# FE2_1.net
KiCad netlist of a schematic drawn in Altium Designer
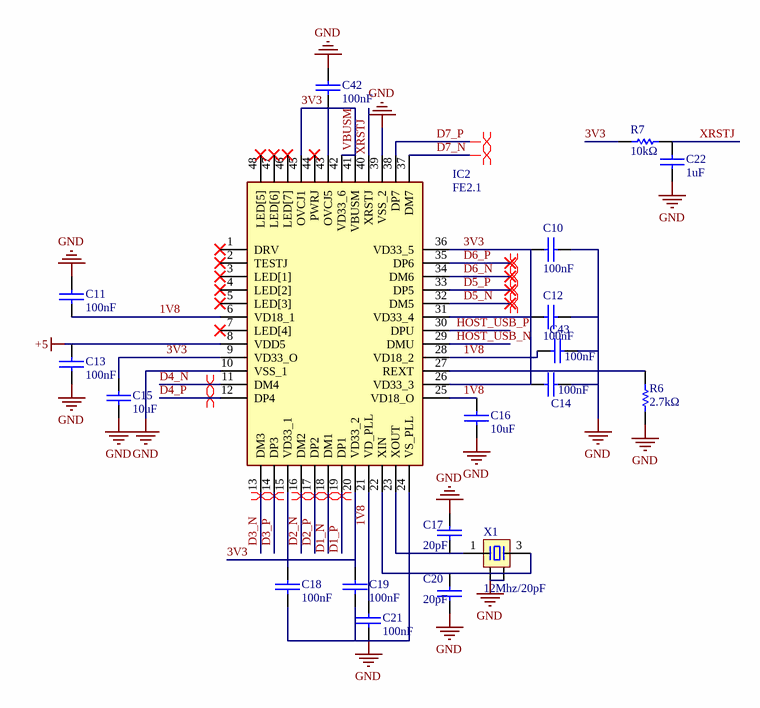
[diagram p0: FE2.1.SchDoc]

(export (version "E")
  (design (tool "Eeschema 10.0.6"))
  (components
    (comp (ref "C10")
      (value "100nF")
      (footprint "C_0402")
      (description "贴片电容")
      (libsource (lib "IntLib-Passive") (part "Cap_Chip"))
    )
    (comp (ref "C11")
      (value "100nF")
      (footprint "C_0402")
      (description "贴片电容")
      (libsource (lib "IntLib-Passive") (part "Cap_Chip"))
    )
    (comp (ref "C12")
      (value "100nF")
      (footprint "C_0402")
      (description "贴片电容")
      (libsource (lib "IntLib-Passive") (part "Cap_Chip"))
    )
    (comp (ref "C13")
      (value "100nF")
      (footprint "C_0402")
      (description "贴片电容")
      (libsource (lib "IntLib-Passive") (part "Cap_Chip"))
    )
    (comp (ref "C14")
      (value "100nF")
      (footprint "C_0402")
      (description "贴片电容")
      (libsource (lib "IntLib-Passive") (part "Cap_Chip"))
    )
    (comp (ref "C15")
      (value "10uF")
      (footprint "C_0603")
      (description "贴片电容")
      (libsource (lib "IntLib-Passive") (part "Cap_Chip"))
    )
    (comp (ref "C16")
      (value "10uF")
      (footprint "C_0603")
      (description "贴片电容")
      (libsource (lib "IntLib-Passive") (part "Cap_Chip"))
    )
    (comp (ref "C17")
      (value "20pF")
      (footprint "C_0402")
      (description "贴片电容")
      (libsource (lib "IntLib-Passive") (part "Cap_Chip"))
    )
    (comp (ref "C18")
      (value "100nF")
      (footprint "C_0402")
      (description "贴片电容")
      (libsource (lib "IntLib-Passive") (part "Cap_Chip"))
    )
    (comp (ref "C19")
      (value "100nF")
      (footprint "C_0402")
      (description "贴片电容")
      (libsource (lib "IntLib-Passive") (part "Cap_Chip"))
    )
    (comp (ref "C20")
      (value "20pF")
      (footprint "C_0402")
      (description "贴片电容")
      (libsource (lib "IntLib-Passive") (part "Cap_Chip"))
    )
    (comp (ref "C21")
      (value "100nF")
      (footprint "C_0402")
      (description "贴片电容")
      (libsource (lib "IntLib-Passive") (part "Cap_Chip"))
    )
    (comp (ref "C22")
      (value "1uF")
      (footprint "C_0402")
      (description "贴片电容")
      (libsource (lib "IntLib-Passive") (part "Cap_Chip"))
    )
    (comp (ref "C42")
      (value "100nF")
      (footprint "C_0402")
      (description "贴片电容")
      (libsource (lib "IntLib-Passive") (part "Cap_Chip"))
    )
    (comp (ref "C43")
      (value "100nF")
      (footprint "C_0402")
      (description "贴片电容")
      (libsource (lib "IntLib-Passive") (part "Cap_Chip"))
    )
    (comp (ref "IC2")
      (value "FE2.1")
      (footprint "IntLib-IC:LQFP48-48_7x7")
      (description "USB2.0 Hub 芯片")
      (fields (field (name "MANUFACTURER_PART_NUMBER") "FE2.1_QFP"))
      (libsource (lib "IntLib-IC") (part "FE2.1_QFP"))
    )
    (comp (ref "R6")
      (value "2.7kΩ")
      (footprint "R_0402")
      (description "贴片电阻")
      (libsource (lib "IntLib-Passive") (part "Res_Chip"))
    )
    (comp (ref "R7")
      (value "10kΩ")
      (footprint "R_0402")
      (description "贴片电阻")
      (libsource (lib "IntLib-Passive") (part "Res_Chip"))
    )
    (comp (ref "X1")
      (value "12Mhz/20pF")
      (footprint "XTAL_3225-4P")
      (description "4脚无源晶振")
      (fields (field (name "MANUFACTURER_PART_NUMBER") "X322512MSB4SI"))
      (libsource (lib "Active-Crystal") (part "Crystal_4P"))
    )
  )
  (nets
    (net (code "1") (name "+5") (class "Default")
      (node (ref "C13") (pin "1") (pinfunction "1_1") (pintype "passive"))
      (node (ref "IC2") (pin "8") (pinfunction "VDD5_8") (pintype "passive"))
    )
    (net (code "2") (name "/1V8") (class "Default")
      (node (ref "C11") (pin "2") (pinfunction "2_2") (pintype "passive"))
      (node (ref "C16") (pin "1") (pinfunction "1_1") (pintype "passive"))
      (node (ref "C21") (pin "1") (pinfunction "1_1") (pintype "passive"))
      (node (ref "C43") (pin "2") (pinfunction "2_2") (pintype "passive"))
      (node (ref "IC2") (pin "21") (pinfunction "VD_PLL_21") (pintype "passive"))
      (node (ref "IC2") (pin "25") (pinfunction "VD18_O_25") (pintype "passive"))
      (node (ref "IC2") (pin "28") (pinfunction "VD18_2_28") (pintype "passive"))
      (node (ref "IC2") (pin "6") (pinfunction "VD18_1_6") (pintype "passive"))
    )
    (net (code "3") (name "/3V3") (class "Default")
      (node (ref "C10") (pin "1") (pinfunction "1_1") (pintype "passive"))
      (node (ref "C12") (pin "2") (pinfunction "2_2") (pintype "passive"))
      (node (ref "C14") (pin "2") (pinfunction "2_2") (pintype "passive"))
      (node (ref "C15") (pin "2") (pinfunction "2_2") (pintype "passive"))
      (node (ref "C18") (pin "1") (pinfunction "1_1") (pintype "passive"))
      (node (ref "C19") (pin "1") (pinfunction "1_1") (pintype "passive"))
      (node (ref "C42") (pin "1") (pinfunction "1_1") (pintype "passive"))
      (node (ref "IC2") (pin "15") (pinfunction "VD33_1_15") (pintype "passive"))
      (node (ref "IC2") (pin "20") (pinfunction "VD33_2_20") (pintype "passive"))
      (node (ref "IC2") (pin "26") (pinfunction "VD33_3_26") (pintype "passive"))
      (node (ref "IC2") (pin "31") (pinfunction "VD33_4_31") (pintype "passive"))
      (node (ref "IC2") (pin "36") (pinfunction "VD33_5_36") (pintype "passive"))
      (node (ref "IC2") (pin "41") (pinfunction "VBUSM_41") (pintype "passive"))
      (node (ref "IC2") (pin "42") (pinfunction "VD33_6_42") (pintype "passive"))
      (node (ref "IC2") (pin "43") (pinfunction "OVCJ5_43") (pintype "passive"))
      (node (ref "IC2") (pin "45") (pinfunction "OVCJ1_45") (pintype "passive"))
      (node (ref "IC2") (pin "9") (pinfunction "VD33_O_9") (pintype "passive"))
      (node (ref "R7") (pin "2") (pinfunction "2_2") (pintype "passive"))
    )
    (net (code "4") (name "/D1_N") (class "Default")
      (node (ref "IC2") (pin "18") (pinfunction "DM1_18") (pintype "passive"))
    )
    (net (code "5") (name "/D1_P") (class "Default")
      (node (ref "IC2") (pin "19") (pinfunction "DP1_19") (pintype "passive"))
    )
    (net (code "6") (name "/D2_N") (class "Default")
      (node (ref "IC2") (pin "16") (pinfunction "DM2_16") (pintype "passive"))
    )
    (net (code "7") (name "/D2_P") (class "Default")
      (node (ref "IC2") (pin "17") (pinfunction "DP2_17") (pintype "passive"))
    )
    (net (code "8") (name "/D3_N") (class "Default")
      (node (ref "IC2") (pin "13") (pinfunction "DM3_13") (pintype "passive"))
    )
    (net (code "9") (name "/D3_P") (class "Default")
      (node (ref "IC2") (pin "14") (pinfunction "DP3_14") (pintype "passive"))
    )
    (net (code "10") (name "/D4_N") (class "Default")
      (node (ref "IC2") (pin "11") (pinfunction "DM4_11") (pintype "passive"))
    )
    (net (code "11") (name "/D4_P") (class "Default")
      (node (ref "IC2") (pin "12") (pinfunction "DP4_12") (pintype "passive"))
    )
    (net (code "12") (name "/D5_N") (class "Default")
      (node (ref "IC2") (pin "32") (pinfunction "DM5_32") (pintype "passive+no_connect"))
    )
    (net (code "13") (name "/D5_P") (class "Default")
      (node (ref "IC2") (pin "33") (pinfunction "DP5_33") (pintype "passive+no_connect"))
    )
    (net (code "14") (name "/D6_N") (class "Default")
      (node (ref "IC2") (pin "34") (pinfunction "DM6_34") (pintype "passive+no_connect"))
    )
    (net (code "15") (name "/D6_P") (class "Default")
      (node (ref "IC2") (pin "35") (pinfunction "DP6_35") (pintype "passive+no_connect"))
    )
    (net (code "16") (name "/D7_N") (class "Default")
      (node (ref "IC2") (pin "37") (pinfunction "DM7_37") (pintype "passive"))
    )
    (net (code "17") (name "/D7_P") (class "Default")
      (node (ref "IC2") (pin "38") (pinfunction "DP7_38") (pintype "passive"))
    )
    (net (code "18") (name "/HOST_USB_N") (class "Default")
      (node (ref "IC2") (pin "29") (pinfunction "DMU_29") (pintype "passive"))
    )
    (net (code "19") (name "/HOST_USB_P") (class "Default")
      (node (ref "IC2") (pin "30") (pinfunction "DPU_30") (pintype "passive"))
    )
    (net (code "20") (name "/XRSTJ") (class "Default")
      (node (ref "C22") (pin "2") (pinfunction "2_2") (pintype "passive"))
      (node (ref "IC2") (pin "40") (pinfunction "XRSTJ_40") (pintype "passive"))
      (node (ref "R7") (pin "1") (pinfunction "1_1") (pintype "passive"))
    )
    (net (code "21") (name "GND") (class "Default")
      (node (ref "C10") (pin "2") (pinfunction "2_2") (pintype "passive"))
      (node (ref "C11") (pin "1") (pinfunction "1_1") (pintype "passive"))
      (node (ref "C12") (pin "1") (pinfunction "1_1") (pintype "passive"))
      (node (ref "C13") (pin "2") (pinfunction "2_2") (pintype "passive"))
      (node (ref "C14") (pin "1") (pinfunction "1_1") (pintype "passive"))
      (node (ref "C15") (pin "1") (pinfunction "1_1") (pintype "passive"))
      (node (ref "C16") (pin "2") (pinfunction "2_2") (pintype "passive"))
      (node (ref "C17") (pin "2") (pinfunction "2_2") (pintype "passive"))
      (node (ref "C18") (pin "2") (pinfunction "2_2") (pintype "passive"))
      (node (ref "C19") (pin "2") (pinfunction "2_2") (pintype "passive"))
      (node (ref "C20") (pin "1") (pinfunction "1_1") (pintype "passive"))
      (node (ref "C21") (pin "2") (pinfunction "2_2") (pintype "passive"))
      (node (ref "C22") (pin "1") (pinfunction "1_1") (pintype "passive"))
      (node (ref "C42") (pin "2") (pinfunction "2_2") (pintype "passive"))
      (node (ref "C43") (pin "1") (pinfunction "1_1") (pintype "passive"))
      (node (ref "IC2") (pin "10") (pinfunction "VSS_1_10") (pintype "passive"))
      (node (ref "IC2") (pin "24") (pinfunction "VS_PLL_24") (pintype "passive"))
      (node (ref "IC2") (pin "39") (pinfunction "VSS_2_39") (pintype "passive"))
      (node (ref "R6") (pin "1") (pinfunction "1_1") (pintype "passive"))
      (node (ref "X1") (pin "2") (pinfunction "2_2") (pintype "passive"))
      (node (ref "X1") (pin "4") (pinfunction "4_4") (pintype "passive"))
    )
    (net (code "22") (name "Net-(IC2-REXT)") (class "Default")
      (node (ref "IC2") (pin "27") (pinfunction "REXT_27") (pintype "passive"))
      (node (ref "R6") (pin "2") (pinfunction "2_2") (pintype "passive"))
    )
    (net (code "23") (name "Net-(IC2-XIN)") (class "Default")
      (node (ref "C20") (pin "2") (pinfunction "2_2") (pintype "passive"))
      (node (ref "IC2") (pin "22") (pinfunction "XIN_22") (pintype "passive"))
      (node (ref "X1") (pin "3") (pinfunction "3_3") (pintype "passive"))
    )
    (net (code "24") (name "Net-(IC2-XOUT)") (class "Default")
      (node (ref "C17") (pin "1") (pinfunction "1_1") (pintype "passive"))
      (node (ref "IC2") (pin "23") (pinfunction "XOUT_23") (pintype "passive"))
      (node (ref "X1") (pin "1") (pinfunction "1_1") (pintype "passive"))
    )
    (net (code "25") (name "unconnected-(IC2-DRV-Pad1)") (class "Default")
      (node (ref "IC2") (pin "1") (pinfunction "DRV_1") (pintype "passive+no_connect"))
    )
    (net (code "26") (name "unconnected-(IC2-LED[1]-Pad3)") (class "Default")
      (node (ref "IC2") (pin "3") (pinfunction "LED[1]_3") (pintype "passive+no_connect"))
    )
    (net (code "27") (name "unconnected-(IC2-LED[2]-Pad4)") (class "Default")
      (node (ref "IC2") (pin "4") (pinfunction "LED[2]_4") (pintype "passive+no_connect"))
    )
    (net (code "28") (name "unconnected-(IC2-LED[3]-Pad5)") (class "Default")
      (node (ref "IC2") (pin "5") (pinfunction "LED[3]_5") (pintype "passive+no_connect"))
    )
    (net (code "29") (name "unconnected-(IC2-LED[4]-Pad7)") (class "Default")
      (node (ref "IC2") (pin "7") (pinfunction "LED[4]_7") (pintype "passive+no_connect"))
    )
    (net (code "30") (name "unconnected-(IC2-LED[5]-Pad48)") (class "Default")
      (node (ref "IC2") (pin "48") (pinfunction "LED[5]_48") (pintype "passive+no_connect"))
    )
    (net (code "31") (name "unconnected-(IC2-LED[6]-Pad47)") (class "Default")
      (node (ref "IC2") (pin "47") (pinfunction "LED[6]_47") (pintype "passive+no_connect"))
    )
    (net (code "32") (name "unconnected-(IC2-LED[7]-Pad46)") (class "Default")
      (node (ref "IC2") (pin "46") (pinfunction "LED[7]_46") (pintype "passive+no_connect"))
    )
    (net (code "33") (name "unconnected-(IC2-PWRJ-Pad44)") (class "Default")
      (node (ref "IC2") (pin "44") (pinfunction "PWRJ_44") (pintype "passive+no_connect"))
    )
    (net (code "34") (name "unconnected-(IC2-TESTJ-Pad2)") (class "Default")
      (node (ref "IC2") (pin "2") (pinfunction "TESTJ_2") (pintype "passive+no_connect"))
    )
  )
)
